# Tunguska.net
KiCad netlist of a schematic drawn in Altium Designer
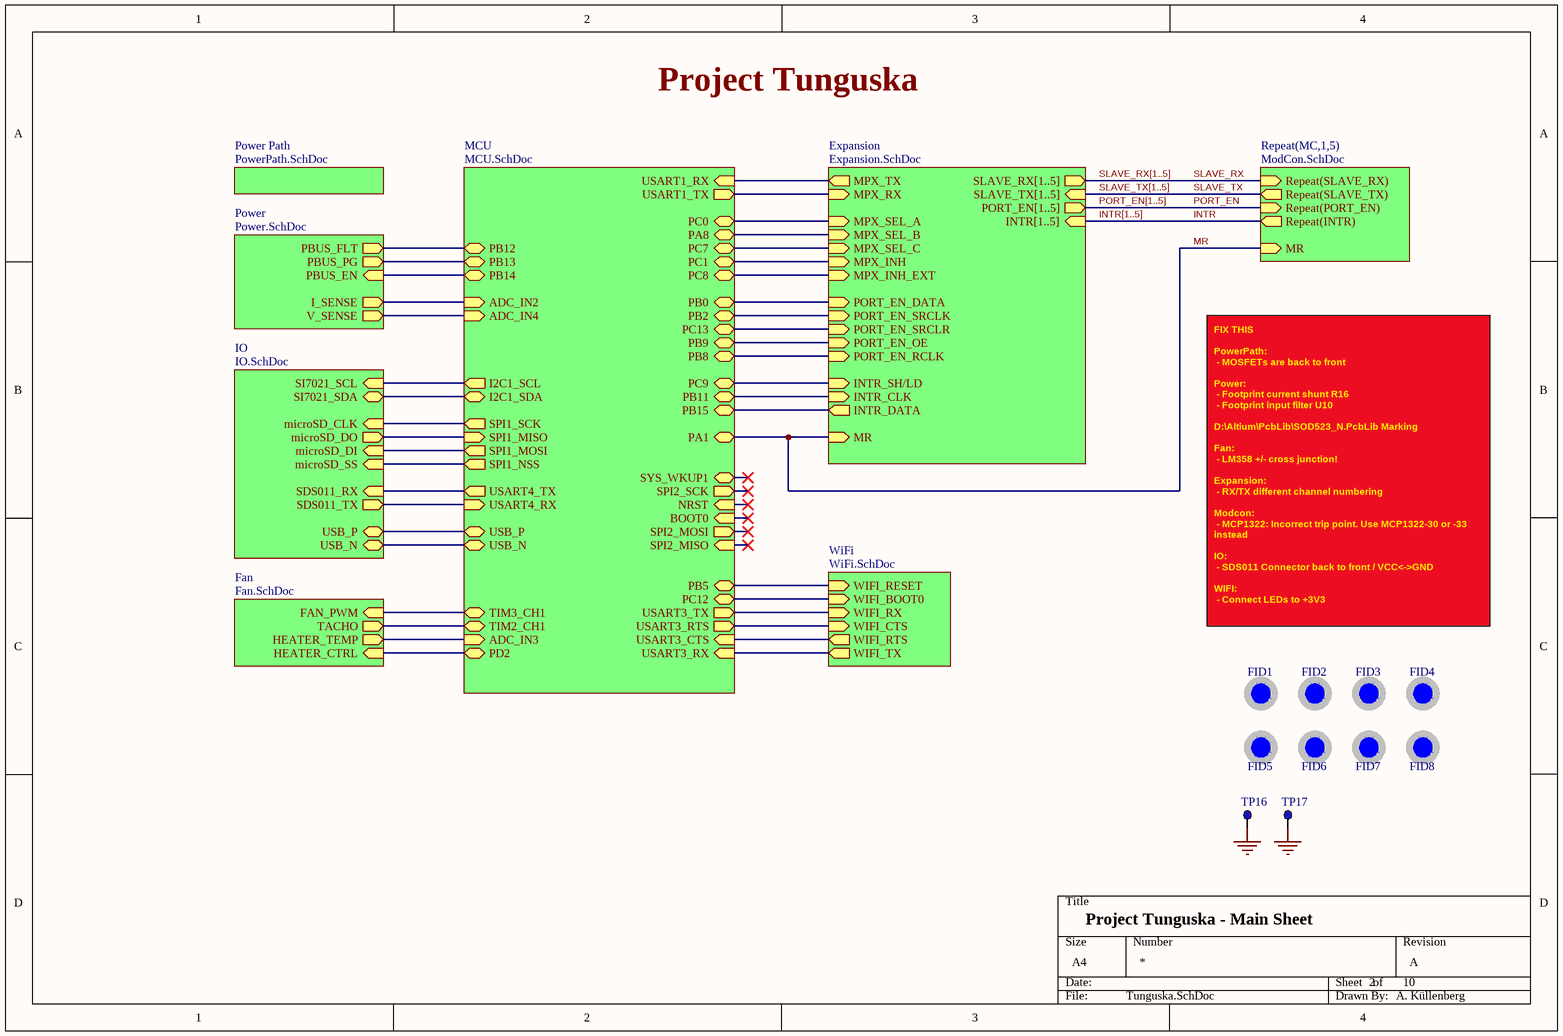
[diagram p0: Tunguska.SchDoc]

(export (version "E")
  (design (tool "Eeschema 10.0.6"))
  (components
    (comp (ref "FID1")
      (value "Standard")
      (footprint "Fiducial_40_120mil")
      (fields (field (name "PART NUMBER") "Fiducial 40/120mil"))
      (libsource (lib "AKLib") (part "Fiducial"))
    )
    (comp (ref "FID2")
      (value "Standard")
      (footprint "Fiducial_40_120mil")
      (fields (field (name "PART NUMBER") "Fiducial 40/120mil"))
      (libsource (lib "AKLib") (part "Fiducial"))
    )
    (comp (ref "FID3")
      (value "Standard")
      (footprint "Fiducial_40_120mil")
      (fields (field (name "PART NUMBER") "Fiducial 40/120mil"))
      (libsource (lib "AKLib") (part "Fiducial"))
    )
    (comp (ref "FID4")
      (value "Standard")
      (footprint "Fiducial_40_120mil")
      (fields (field (name "PART NUMBER") "Fiducial 40/120mil"))
      (libsource (lib "AKLib") (part "Fiducial"))
    )
    (comp (ref "FID5")
      (value "Standard")
      (footprint "Fiducial_40_120mil")
      (fields (field (name "PART NUMBER") "Fiducial 40/120mil"))
      (libsource (lib "AKLib") (part "Fiducial"))
    )
    (comp (ref "FID6")
      (value "Standard")
      (footprint "Fiducial_40_120mil")
      (fields (field (name "PART NUMBER") "Fiducial 40/120mil"))
      (libsource (lib "AKLib") (part "Fiducial"))
    )
    (comp (ref "FID7")
      (value "Standard")
      (footprint "Fiducial_40_120mil")
      (fields (field (name "PART NUMBER") "Fiducial 40/120mil"))
      (libsource (lib "AKLib") (part "Fiducial"))
    )
    (comp (ref "FID8")
      (value "Standard")
      (footprint "Fiducial_40_120mil")
      (fields (field (name "PART NUMBER") "Fiducial 40/120mil"))
      (libsource (lib "AKLib") (part "Fiducial"))
    )
    (comp (ref "TP16")
      (value "TP")
      (footprint "TP_TH")
      (description "TEST POINT PC MINI .040\"D BLACK")
      (fields (field (name "PART NUMBER") "5001") (field (name "MANUFACTURER") "Keystone Electronics"))
      (libsource (lib "AKLib") (part "TP"))
    )
    (comp (ref "TP17")
      (value "TP")
      (footprint "TP_TH")
      (description "TEST POINT PC MINI .040\"D BLACK")
      (fields (field (name "PART NUMBER") "5001") (field (name "MANUFACTURER") "Keystone Electronics"))
      (libsource (lib "AKLib") (part "TP"))
    )
  )
  (nets
    (net (code "76") (name "GND") (class "Default")
      (node (ref "TP16") (pin "1") (pinfunction "1_1") (pintype "passive"))
      (node (ref "TP17") (pin "1") (pinfunction "1_1") (pintype "passive"))
    )
  )
)
